# TIDA-01576_ADS8686S_AFE_Pg4-5V-15V_Split.net
KiCad netlist of a schematic drawn in Altium Designer
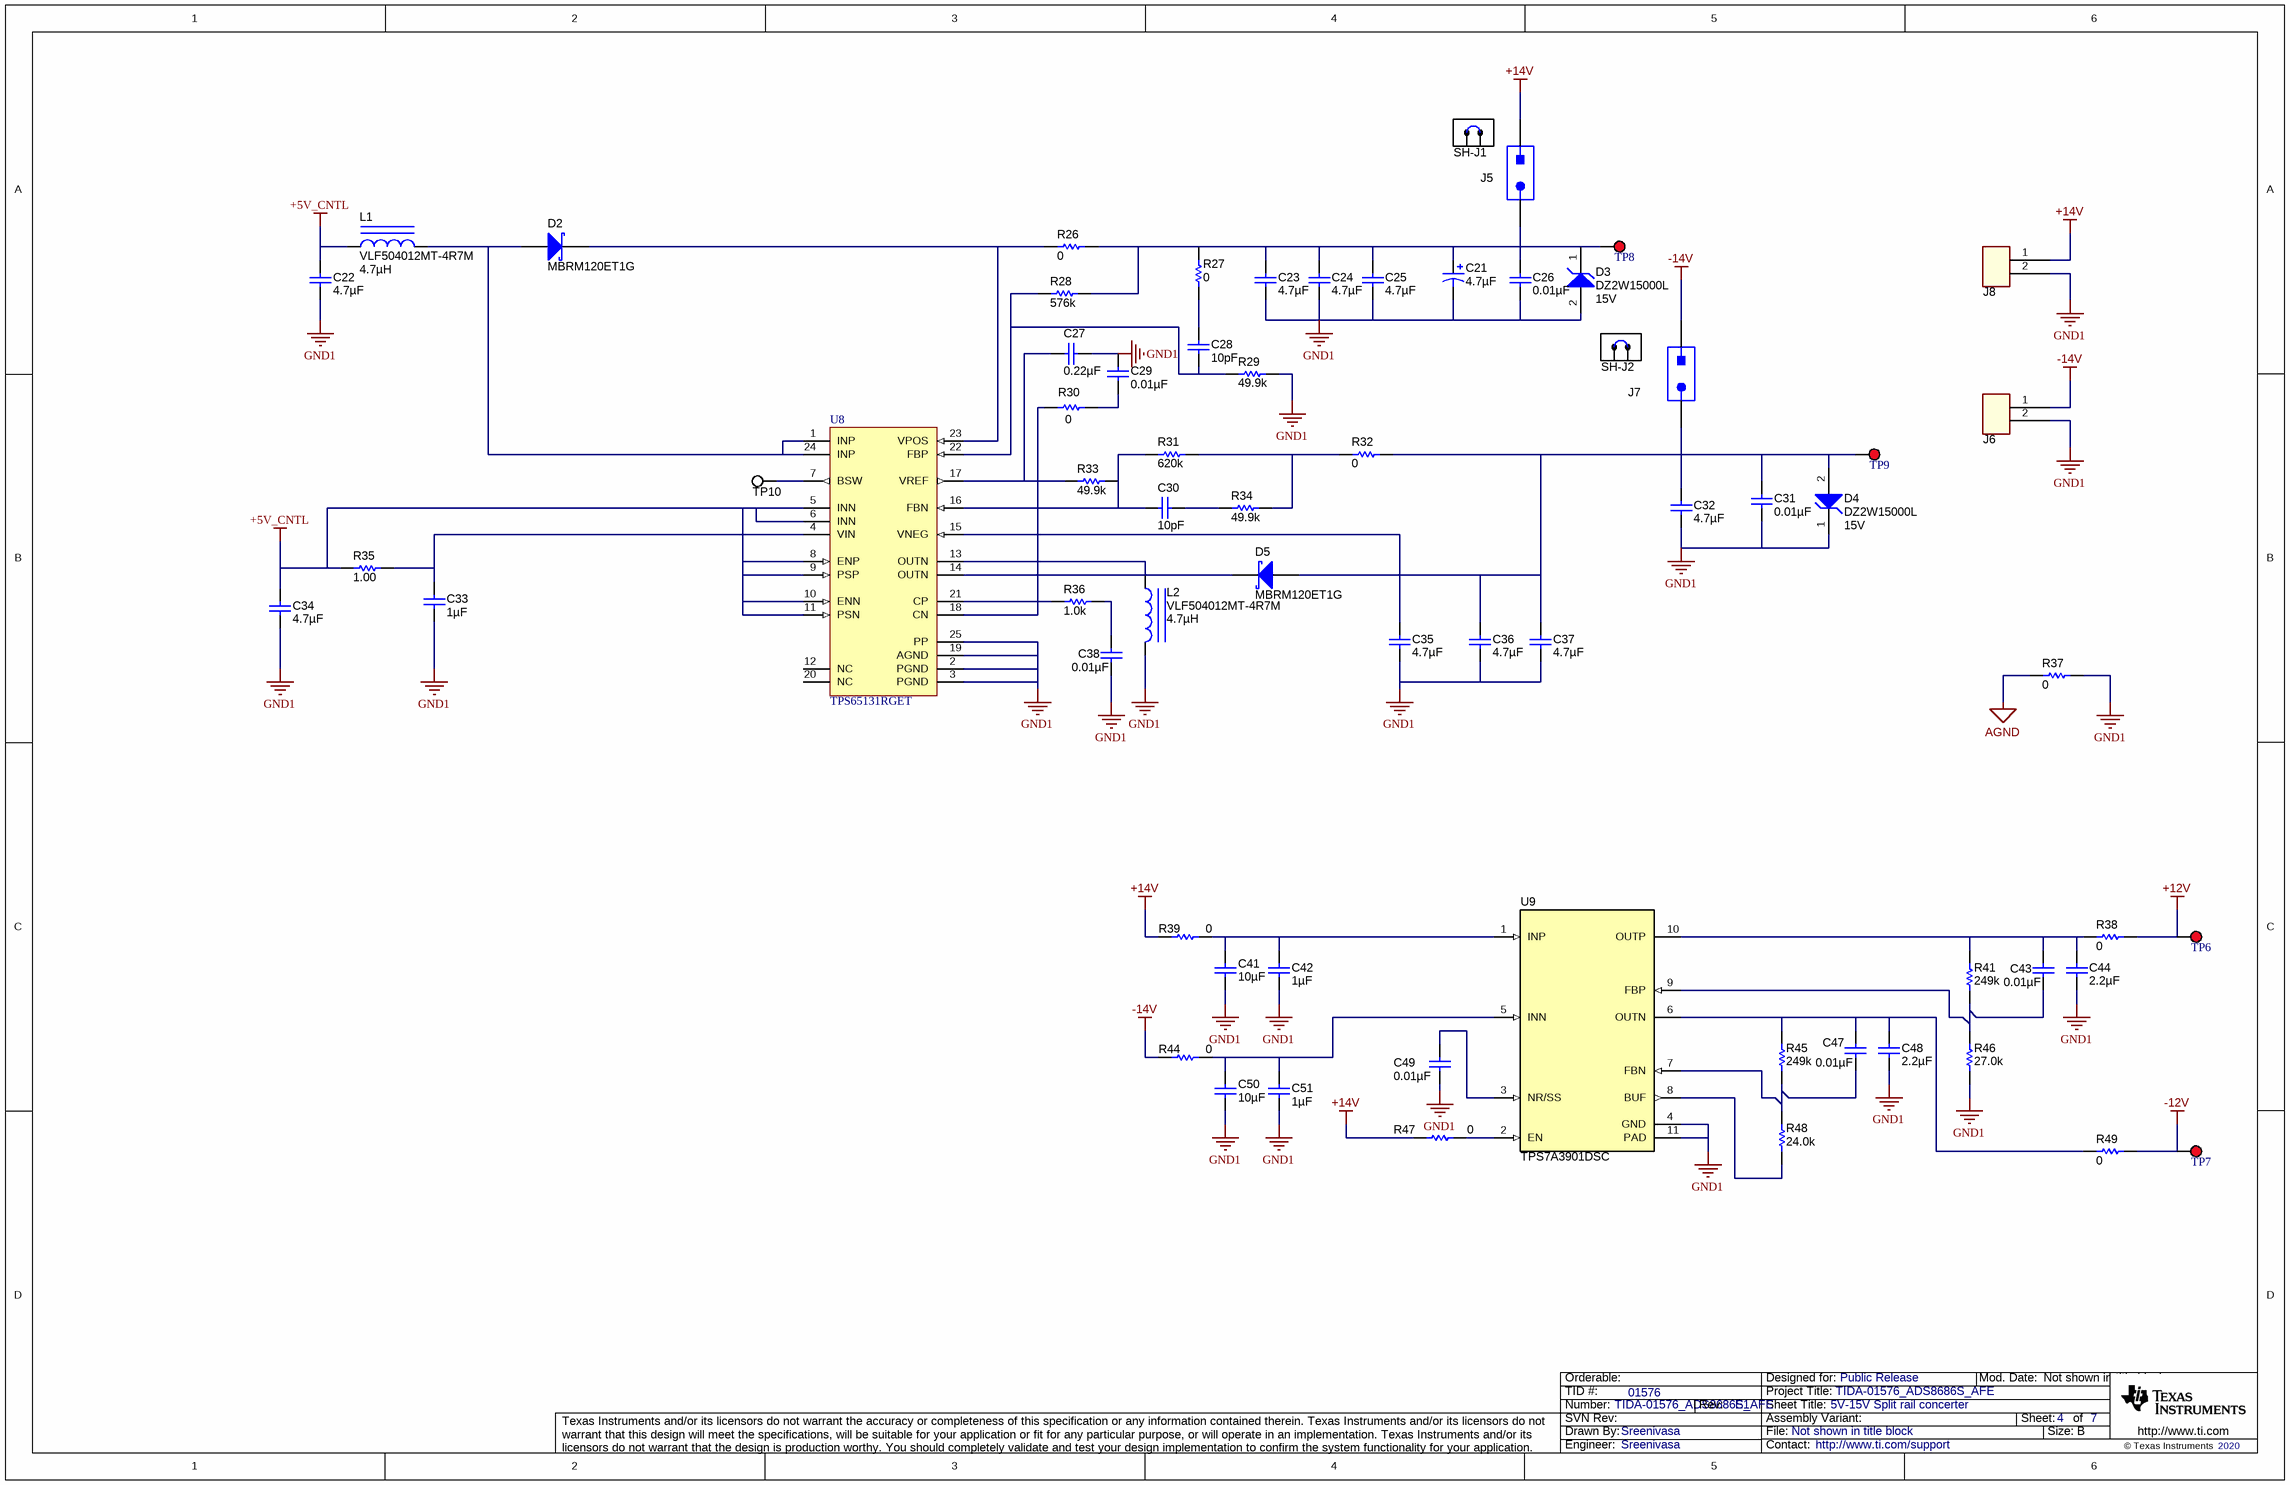
[diagram p0: TIDA-01576_ADS8686S_AFE_Pg4-5V-15V Split rail converter.SchDoc]

(export (version "E")
  (design (tool "Eeschema 10.0.6"))
  (components
    (comp (ref "C21")
      (value "293D475X9025C2TE3")
      (footprint "6032-28")
      (description "CAP, TA, 4.7 µF, 25 V, +/- 10%, 2 ohm, SMD")
      (fields
        (field (name "VALUEDISPLAYED") "4.7µF")
        (field (name "MANUFACTURER") "Vishay-Sprague")
        (field (name "PUBLISHER") "Texas Instruments")
      )
      (libsource (lib "Capacitor_Tantalum") (part "293D475X9025C2TE3"))
    )
    (comp (ref "C22")
      (value "C3216X7R1E475M160AC")
      (footprint "1206")
      (description "CAP, CERM, 4.7 µF, 25 V, +/- 20%, X7R, 1206")
      (fields
        (field (name "VALUEDISPLAYED") "4.7µF")
        (field (name "MANUFACTURER") "TDK")
        (field (name "PUBLISHER") "Texas Instruments")
      )
      (libsource (lib "Capacitor_Ceramic") (part "C3216X7R1E475M"))
    )
    (comp (ref "C23")
      (value "C3216X7R1E475M160AC")
      (footprint "1206")
      (description "CAP, CERM, 4.7 µF, 25 V, +/- 20%, X7R, 1206")
      (fields
        (field (name "VALUEDISPLAYED") "4.7µF")
        (field (name "MANUFACTURER") "TDK")
        (field (name "PUBLISHER") "Texas Instruments")
      )
      (libsource (lib "Capacitor_Ceramic") (part "C3216X7R1E475M"))
    )
    (comp (ref "C24")
      (value "C3216X7R1E475M160AC")
      (footprint "1206")
      (description "CAP, CERM, 4.7 µF, 25 V, +/- 20%, X7R, 1206")
      (fields
        (field (name "VALUEDISPLAYED") "4.7µF")
        (field (name "MANUFACTURER") "TDK")
        (field (name "PUBLISHER") "Texas Instruments")
      )
      (libsource (lib "Capacitor_Ceramic") (part "C3216X7R1E475M"))
    )
    (comp (ref "C25")
      (value "C3216X7R1E475M160AC")
      (footprint "1206")
      (description "CAP, CERM, 4.7 µF, 25 V, +/- 20%, X7R, 1206")
      (fields
        (field (name "VALUEDISPLAYED") "4.7µF")
        (field (name "MANUFACTURER") "TDK")
        (field (name "PUBLISHER") "Texas Instruments")
      )
      (libsource (lib "Capacitor_Ceramic") (part "C3216X7R1E475M"))
    )
    (comp (ref "C26")
      (value "GRM188R70J103KA01D")
      (footprint "0603")
      (description "CAP, CERM, 0.01 µF, 6.3 V, +/- 10%, X7R, 0603")
      (fields
        (field (name "VALUEDISPLAYED") "0.01µF")
        (field (name "MANUFACTURER") "MuRata")
        (field (name "PUBLISHER") "Texas Instruments")
      )
      (libsource (lib "Capacitor_Ceramic") (part "GRM188R70J103KA01D"))
    )
    (comp (ref "C27")
      (value "C0603C224K9RACTU")
      (footprint "0603")
      (description "CAP, CERM, 0.22 µF, 6.3 V, +/- 10%, X7R, 0603")
      (fields
        (field (name "VALUEDISPLAYED") "0.22µF")
        (field (name "MANUFACTURER") "Kemet")
        (field (name "PUBLISHER") "Texas Instruments")
      )
      (libsource (lib "Capacitor_Ceramic") (part "C0603C224K4RACTU"))
    )
    (comp (ref "C28")
      (value "C0603C100J5GACTU")
      (footprint "0603")
      (description "CAP, CERM, 10 pF, 50 V, +/- 5%, C0G/NP0, 0603")
      (fields
        (field (name "VALUEDISPLAYED") "10pF")
        (field (name "MANUFACTURER") "Kemet")
        (field (name "PUBLISHER") "Texas Instruments")
      )
      (libsource (lib "Capacitor_Ceramic") (part "C0603C100J5GACTU"))
    )
    (comp (ref "C29")
      (value "GRM188R70J103KA01D")
      (footprint "0603")
      (description "CAP, CERM, 0.01 µF, 6.3 V, +/- 10%, X7R, 0603")
      (fields
        (field (name "VALUEDISPLAYED") "0.01µF")
        (field (name "MANUFACTURER") "MuRata")
        (field (name "PUBLISHER") "Texas Instruments")
      )
      (libsource (lib "Capacitor_Ceramic") (part "GRM188R70J103KA01D"))
    )
    (comp (ref "C30")
      (value "C0603C100J5GACTU")
      (footprint "0603")
      (description "CAP, CERM, 10 pF, 50 V, +/- 5%, C0G/NP0, 0603")
      (fields
        (field (name "VALUEDISPLAYED") "10pF")
        (field (name "MANUFACTURER") "Kemet")
        (field (name "PUBLISHER") "Texas Instruments")
      )
      (libsource (lib "Capacitor_Ceramic") (part "C0603C100J5GACTU"))
    )
    (comp (ref "C31")
      (value "GRM188R70J103KA01D")
      (footprint "0603")
      (description "CAP, CERM, 0.01 µF, 6.3 V, +/- 10%, X7R, 0603")
      (fields
        (field (name "VALUEDISPLAYED") "0.01µF")
        (field (name "MANUFACTURER") "MuRata")
        (field (name "PUBLISHER") "Texas Instruments")
      )
      (libsource (lib "Capacitor_Ceramic") (part "GRM188R70J103KA01D"))
    )
    (comp (ref "C32")
      (value "C3216X7R1E475M160AC")
      (footprint "1206")
      (description "CAP, CERM, 4.7 µF, 25 V, +/- 20%, X7R, 1206")
      (fields
        (field (name "VALUEDISPLAYED") "4.7µF")
        (field (name "MANUFACTURER") "TDK")
        (field (name "PUBLISHER") "Texas Instruments")
      )
      (libsource (lib "Capacitor_Ceramic") (part "C3216X7R1E475M"))
    )
    (comp (ref "C33")
      (value "GRM188R61E105KA12D")
      (footprint "0603")
      (description "CAP, CERM, 1 µF, 25 V, +/- 10%, X5R, 0603")
      (fields
        (field (name "VALUEDISPLAYED") "1µF")
        (field (name "MANUFACTURER") "MuRata")
        (field (name "PUBLISHER") "Texas Instruments")
      )
      (libsource (lib "Capacitor_Ceramic") (part "GRM188R61E105KA12D"))
    )
    (comp (ref "C34")
      (value "C3216X7R1E475M160AC")
      (footprint "1206")
      (description "CAP, CERM, 4.7 µF, 25 V, +/- 20%, X7R, 1206")
      (fields
        (field (name "VALUEDISPLAYED") "4.7µF")
        (field (name "MANUFACTURER") "TDK")
        (field (name "PUBLISHER") "Texas Instruments")
      )
      (libsource (lib "Capacitor_Ceramic") (part "C3216X7R1E475M"))
    )
    (comp (ref "C35")
      (value "C3216X7R1E475M160AC")
      (footprint "1206")
      (description "CAP, CERM, 4.7 µF, 25 V, +/- 20%, X7R, 1206")
      (fields
        (field (name "VALUEDISPLAYED") "4.7µF")
        (field (name "MANUFACTURER") "TDK")
        (field (name "PUBLISHER") "Texas Instruments")
      )
      (libsource (lib "Capacitor_Ceramic") (part "C3216X7R1E475M"))
    )
    (comp (ref "C36")
      (value "C3216X7R1E475M160AC")
      (footprint "1206")
      (description "CAP, CERM, 4.7 µF, 25 V, +/- 20%, X7R, 1206")
      (fields
        (field (name "VALUEDISPLAYED") "4.7µF")
        (field (name "MANUFACTURER") "TDK")
        (field (name "PUBLISHER") "Texas Instruments")
      )
      (libsource (lib "Capacitor_Ceramic") (part "C3216X7R1E475M"))
    )
    (comp (ref "C37")
      (value "C3216X7R1E475M160AC")
      (footprint "1206")
      (description "CAP, CERM, 4.7 µF, 25 V, +/- 20%, X7R, 1206")
      (fields
        (field (name "VALUEDISPLAYED") "4.7µF")
        (field (name "MANUFACTURER") "TDK")
        (field (name "PUBLISHER") "Texas Instruments")
      )
      (libsource (lib "Capacitor_Ceramic") (part "C3216X7R1E475M"))
    )
    (comp (ref "C38")
      (value "GRM188R70J103KA01D")
      (footprint "0603")
      (description "CAP, CERM, 0.01 µF, 6.3 V, +/- 10%, X7R, 0603")
      (fields
        (field (name "VALUEDISPLAYED") "0.01µF")
        (field (name "MANUFACTURER") "MuRata")
        (field (name "PUBLISHER") "Texas Instruments")
      )
      (libsource (lib "Capacitor_Ceramic") (part "GRM188R70J103KA01D"))
    )
    (comp (ref "C41")
      (value "~")
      (footprint "1210")
      (description "CAP, CERM, 10uF, 35V, +/-20%, X7R, 1210")
      (fields
        (field (name "PARTNUMBER") "GMK325AB7106MM-T")
        (field (name "VALUEDISPLAYED") "10µF")
        (field (name "MANUFACTURER") "Taiyo Yuden")
        (field (name "PUBLISHER") "Texas Instruments")
      )
      (libsource (lib "Capacitor_Ceramic") (part "GMK325AB7106MM-T"))
    )
    (comp (ref "C42")
      (value "GRM188R61E105KA12D")
      (footprint "0603")
      (description "CAP, CERM, 1 µF, 25 V, +/- 10%, X5R, 0603")
      (fields
        (field (name "VALUEDISPLAYED") "1µF")
        (field (name "MANUFACTURER") "MuRata")
        (field (name "PUBLISHER") "Texas Instruments")
      )
      (libsource (lib "Capacitor_Ceramic") (part "GRM188R61E105KA12D"))
    )
    (comp (ref "C43")
      (value "GRM188R70J103KA01D")
      (footprint "0603")
      (description "CAP, CERM, 0.01 µF, 6.3 V, +/- 10%, X7R, 0603")
      (fields
        (field (name "VALUEDISPLAYED") "0.01µF")
        (field (name "MANUFACTURER") "MuRata")
        (field (name "PUBLISHER") "Texas Instruments")
      )
      (libsource (lib "Capacitor_Ceramic") (part "GRM188R70J103KA01D"))
    )
    (comp (ref "C44")
      (value "C0805C225K8RACTU")
      (footprint "0805_HV")
      (description "CAP, CERM, 2.2uF, 10V, +/-10%, X7R, 0805")
      (fields
        (field (name "VALUEDISPLAYED") "2.2µF")
        (field (name "MANUFACTURER") "Kemet")
        (field (name "PUBLISHER") "Texas Instruments")
      )
      (libsource (lib "Capacitor_Ceramic") (part "C0805C225K8RACTU"))
    )
    (comp (ref "C47")
      (value "GRM188R70J103KA01D")
      (footprint "0603")
      (description "CAP, CERM, 0.01 µF, 6.3 V, +/- 10%, X7R, 0603")
      (fields
        (field (name "VALUEDISPLAYED") "0.01µF")
        (field (name "MANUFACTURER") "MuRata")
        (field (name "PUBLISHER") "Texas Instruments")
      )
      (libsource (lib "Capacitor_Ceramic") (part "GRM188R70J103KA01D"))
    )
    (comp (ref "C48")
      (value "C0805C225K8RACTU")
      (footprint "0805_HV")
      (description "CAP, CERM, 2.2uF, 10V, +/-10%, X7R, 0805")
      (fields
        (field (name "VALUEDISPLAYED") "2.2µF")
        (field (name "MANUFACTURER") "Kemet")
        (field (name "PUBLISHER") "Texas Instruments")
      )
      (libsource (lib "Capacitor_Ceramic") (part "C0805C225K8RACTU"))
    )
    (comp (ref "C49")
      (value "GRM188R70J103KA01D")
      (footprint "0603")
      (description "CAP, CERM, 0.01 µF, 6.3 V, +/- 10%, X7R, 0603")
      (fields
        (field (name "VALUEDISPLAYED") "0.01µF")
        (field (name "MANUFACTURER") "MuRata")
        (field (name "PUBLISHER") "Texas Instruments")
      )
      (libsource (lib "Capacitor_Ceramic") (part "GRM188R70J103KA01D"))
    )
    (comp (ref "C50")
      (value "~")
      (footprint "1210")
      (description "CAP, CERM, 10uF, 35V, +/-20%, X7R, 1210")
      (fields
        (field (name "PARTNUMBER") "GMK325AB7106MM-T")
        (field (name "VALUEDISPLAYED") "10µF")
        (field (name "MANUFACTURER") "Taiyo Yuden")
        (field (name "PUBLISHER") "Texas Instruments")
      )
      (libsource (lib "Capacitor_Ceramic") (part "GMK325AB7106MM-T"))
    )
    (comp (ref "C51")
      (value "GRM188R61E105KA12D")
      (footprint "0603")
      (description "CAP, CERM, 1 µF, 25 V, +/- 10%, X5R, 0603")
      (fields
        (field (name "VALUEDISPLAYED") "1µF")
        (field (name "MANUFACTURER") "MuRata")
        (field (name "PUBLISHER") "Texas Instruments")
      )
      (libsource (lib "Capacitor_Ceramic") (part "GRM188R61E105KA12D"))
    )
    (comp (ref "D2")
      (value "MBRM120ET1G")
      (footprint "POWERMITE")
      (description "Diode, Schottky, 20 V, 1 A, POWERMITE")
      (fields (field (name "MANUFACTURER") "ON Semiconductor") (field (name "PUBLISHER") "Texas Instruments"))
      (libsource (lib "Diode") (part "MBRM120ET1G"))
    )
    (comp (ref "D3")
      (value "DZ2W15000L")
      (footprint "SOD-123")
      (description "Diode, Zener, 15V, 1W, SOD-123")
      (fields
        (field (name "MANUFACTURER") "Panasonic")
        (field (name "ALTIUM_VALUE") "15V")
        (field (name "PUBLISHER") "Texas Instruments")
      )
      (libsource (lib "TI-INDIA-ALTIUM") (part "DZ2W15000L"))
    )
    (comp (ref "D4")
      (value "DZ2W15000L")
      (footprint "SOD-123")
      (description "Diode, Zener, 15V, 1W, SOD-123")
      (fields
        (field (name "MANUFACTURER") "Panasonic")
        (field (name "ALTIUM_VALUE") "15V")
        (field (name "PUBLISHER") "Texas Instruments")
      )
      (libsource (lib "TI-INDIA-ALTIUM") (part "DZ2W15000L"))
    )
    (comp (ref "D5")
      (value "MBRM120ET1G")
      (footprint "POWERMITE")
      (description "Diode, Schottky, 20 V, 1 A, POWERMITE")
      (fields (field (name "MANUFACTURER") "ON Semiconductor") (field (name "PUBLISHER") "Texas Instruments"))
      (libsource (lib "Diode") (part "MBRM120ET1G"))
    )
    (comp (ref "J5")
      (value "5-146280-2")
      (footprint "TSW-102-07-G-S")
      (description "Header, 100mil, 2x1, Gold, TH")
      (fields
        (field (name "MANUFACTURER") "TE Connectivity")
        (field (name "SYMBOLCREATOR") "a0412235")
        (field (name "PUBLISHER") "Texas Instruments")
      )
      (libsource (lib "Connectors_Samtec") (part "TSW-102-07-G-S"))
    )
    (comp (ref "J6")
      (value "CON-OSTVN02A150")
      (footprint "CN2_MTB_P100_PD80_D1.1_S5.54X6.5_STACK")
      (description "Terminal Block, 4x1, 2.54mm, TH")
      (fields
        (field (name "PARTNUMBER") "OSTVN02A150")
        (field (name "MANUFACTURER") "On Shore Technology Inc")
        (field (name "SYMBOLCREATOR") "x0120606")
        (field (name "PUBLISHER") "TI")
      )
      (libsource (lib "TI-INDIA-ALTIUM") (part "CON-OSTVN02A150"))
    )
    (comp (ref "J7")
      (value "5-146280-2")
      (footprint "TSW-102-07-G-S")
      (description "Header, 100mil, 2x1, Gold, TH")
      (fields
        (field (name "MANUFACTURER") "TE Connectivity")
        (field (name "SYMBOLCREATOR") "a0412235")
        (field (name "PUBLISHER") "Texas Instruments")
      )
      (libsource (lib "Connectors_Samtec") (part "TSW-102-07-G-S"))
    )
    (comp (ref "J8")
      (value "CON-OSTVN02A150")
      (footprint "CN2_MTB_P100_PD80_D1.1_S5.54X6.5_STACK")
      (description "Terminal Block, 4x1, 2.54mm, TH")
      (fields
        (field (name "PARTNUMBER") "OSTVN02A150")
        (field (name "MANUFACTURER") "On Shore Technology Inc")
        (field (name "SYMBOLCREATOR") "x0120606")
        (field (name "PUBLISHER") "TI")
      )
      (libsource (lib "TI-INDIA-ALTIUM") (part "CON-OSTVN02A150"))
    )
    (comp (ref "L1")
      (value "VLF504012MT-4R7M")
      (footprint "IND_VLF504012")
      (description "Inductor, Shielded, Ferrite, 4.7uH, 1.83A, 0.1 ohm, SMD")
      (fields
        (field (name "VALUEDISPLAYED") "4.7µH")
        (field (name "MANUFACTURER") "TDK")
        (field (name "PUBLISHER") "Texas Instruments")
      )
      (libsource (lib "Inductor") (part "VLF504012MT-4R7M"))
    )
    (comp (ref "L2")
      (value "VLF504012MT-4R7M")
      (footprint "IND_VLF504012")
      (description "Inductor, Shielded, Ferrite, 4.7uH, 1.83A, 0.1 ohm, SMD")
      (fields
        (field (name "VALUEDISPLAYED") "4.7µH")
        (field (name "MANUFACTURER") "TDK")
        (field (name "PUBLISHER") "Texas Instruments")
      )
      (libsource (lib "Inductor") (part "VLF504012MT-4R7M"))
    )
    (comp (ref "R26")
      (value "0")
      (footprint "1206")
      (description "RES, 0 ohm, 5%, 0.25W, 1206")
      (fields
        (field (name "PARTNUMBER") "CRCW12060000Z0EA")
        (field (name "MANUFACTURER") "Vishay-Dale")
        (field (name "PUBLISHER") "Texas Instruments")
      )
      (libsource (lib "Resistor_1206") (part "CRCW12060000Z0EA"))
    )
    (comp (ref "R27")
      (value "CRCW06030000Z0EA")
      (footprint "0603")
      (description "RES, 0, 5%, 0.1 W, 0603")
      (fields
        (field (name "VALUEDISPLAYED") "0")
        (field (name "MANUFACTURER") "Vishay-Dale")
        (field (name "PUBLISHER") "Texas Instruments")
      )
      (libsource (lib "Resistor_0603") (part "CRCW06030000Z0EA"))
    )
    (comp (ref "R28")
      (value "CRCW0603576KFKEA")
      (footprint "0603")
      (description "RES, 576 k, 1%, 0.1 W, 0603")
      (fields
        (field (name "VALUEDISPLAYED") "576k")
        (field (name "MANUFACTURER") "Vishay-Dale")
        (field (name "PUBLISHER") "Texas Instruments")
      )
      (libsource (lib "Resistor_0603") (part "CRCW0603576KFKEA"))
    )
    (comp (ref "R29")
      (value "RG1608P-4992-B-T5")
      (footprint "0603")
      (description "RES, 49.9 k, 0.1%, 0.1 W, 0603")
      (fields
        (field (name "VALUEDISPLAYED") "49.9k")
        (field (name "MANUFACTURER") "Susumu Co Ltd")
        (field (name "PUBLISHER") "Texas Instruments")
      )
      (libsource (lib "Resistor_0603") (part "RG1608P-4992-B-T5"))
    )
    (comp (ref "R30")
      (value "CRCW06030000Z0EA")
      (footprint "0603")
      (description "RES, 0, 5%, 0.1 W, 0603")
      (fields
        (field (name "VALUEDISPLAYED") "0")
        (field (name "MANUFACTURER") "Vishay-Dale")
        (field (name "PUBLISHER") "Texas Instruments")
      )
      (libsource (lib "Resistor_0603") (part "CRCW06030000Z0EA"))
    )
    (comp (ref "R31")
      (value "CRCW0603620KFKEA")
      (footprint "0603")
      (description "RES SMD 620K OHM 1% 1/10W 0603")
      (fields
        (field (name "VALUEDISPLAYED") "620k")
        (field (name "MANUFACTURER") "Vishay-Dale")
        (field (name "PUBLISHER") "Texas Instruments")
      )
      (libsource (lib "Resistor_0603") (part "RC0603FR-07620KL"))
    )
    (comp (ref "R32")
      (value "CRCW06030000Z0EA")
      (footprint "0603")
      (description "RES, 0, 5%, 0.1 W, 0603")
      (fields
        (field (name "VALUEDISPLAYED") "0")
        (field (name "MANUFACTURER") "Vishay-Dale")
        (field (name "PUBLISHER") "Texas Instruments")
      )
      (libsource (lib "Resistor_0603") (part "CRCW06030000Z0EA"))
    )
    (comp (ref "R33")
      (value "RG1608P-4992-B-T5")
      (footprint "0603")
      (description "RES, 49.9 k, 0.1%, 0.1 W, 0603")
      (fields
        (field (name "VALUEDISPLAYED") "49.9k")
        (field (name "MANUFACTURER") "Susumu Co Ltd")
        (field (name "PUBLISHER") "Texas Instruments")
      )
      (libsource (lib "Resistor_0603") (part "RG1608P-4992-B-T5"))
    )
    (comp (ref "R34")
      (value "RG1608P-4992-B-T5")
      (footprint "0603")
      (description "RES, 49.9 k, 0.1%, 0.1 W, 0603")
      (fields
        (field (name "VALUEDISPLAYED") "49.9k")
        (field (name "MANUFACTURER") "Susumu Co Ltd")
        (field (name "PUBLISHER") "Texas Instruments")
      )
      (libsource (lib "Resistor_0603") (part "RG1608P-4992-B-T5"))
    )
    (comp (ref "R35")
      (value "CR0603-J/-1R0ELF")
      (footprint "0603")
      (description "RES SMD 1 OHM 5% 1/10W 0603")
      (fields
        (field (name "VALUEDISPLAYED") "1.00")
        (field (name "MANUFACTURER") "Bourns inc")
        (field (name "PUBLISHER") "Texas Instruments")
      )
      (libsource (lib "Resistor_0603") (part "RT0603DRE071RL"))
    )
    (comp (ref "R36")
      (value "CRCW06031K00JNEA")
      (footprint "0603")
      (description "RES, 1.0 k, 5%, 0.1 W, 0603")
      (fields
        (field (name "VALUEDISPLAYED") "1.0k")
        (field (name "MANUFACTURER") "Vishay-Dale")
        (field (name "PUBLISHER") "Texas Instruments")
      )
      (libsource (lib "Resistor_0603") (part "CRCW06031K00JNEA"))
    )
    (comp (ref "R37")
      (value "0")
      (footprint "0805_HV")
      (description "RES, 0 ohm, 5%, 0.125W, 0805")
      (fields
        (field (name "PARTNUMBER") "CRCW08050000Z0EA")
        (field (name "MANUFACTURER") "Vishay-Dale")
        (field (name "PUBLISHER") "Texas Instruments")
      )
      (libsource (lib "Resistor_0805") (part "CRCW0805330KJNEA"))
    )
    (comp (ref "R38")
      (value "CRCW06030000Z0EA")
      (footprint "0603")
      (description "RES, 0, 5%, 0.1 W, 0603")
      (fields
        (field (name "VALUEDISPLAYED") "0")
        (field (name "MANUFACTURER") "Vishay-Dale")
        (field (name "PUBLISHER") "Texas Instruments")
      )
      (libsource (lib "Resistor_0603") (part "CRCW06030000Z0EA"))
    )
    (comp (ref "R39")
      (value "CRCW06030000Z0EA")
      (footprint "0603")
      (description "RES, 0, 5%, 0.1 W, 0603")
      (fields
        (field (name "VALUEDISPLAYED") "0")
        (field (name "MANUFACTURER") "Vishay-Dale")
        (field (name "PUBLISHER") "Texas Instruments")
      )
      (libsource (lib "Resistor_0603") (part "CRCW06030000Z0EA"))
    )
    (comp (ref "R41")
      (value "CRCW0603249KFKEA")
      (footprint "0603")
      (description "RES, 249 k, 1%, 0.1 W, 0603")
      (fields
        (field (name "VALUEDISPLAYED") "249k")
        (field (name "MANUFACTURER") "Vishay-Dale")
        (field (name "PUBLISHER") "Texas Instruments")
      )
      (libsource (lib "Resistor_0603") (part "CRCW0603249KFKEA"))
    )
    (comp (ref "R44")
      (value "CRCW06030000Z0EA")
      (footprint "0603")
      (description "RES, 0, 5%, 0.1 W, 0603")
      (fields
        (field (name "VALUEDISPLAYED") "0")
        (field (name "MANUFACTURER") "Vishay-Dale")
        (field (name "PUBLISHER") "Texas Instruments")
      )
      (libsource (lib "Resistor_0603") (part "CRCW06030000Z0EA"))
    )
    (comp (ref "R45")
      (value "CRCW0603249KFKEA")
      (footprint "0603")
      (description "RES, 249 k, 1%, 0.1 W, 0603")
      (fields
        (field (name "VALUEDISPLAYED") "249k")
        (field (name "MANUFACTURER") "Vishay-Dale")
        (field (name "PUBLISHER") "Texas Instruments")
      )
      (libsource (lib "Resistor_0603") (part "CRCW0603249KFKEA"))
    )
    (comp (ref "R46")
      (value "RC0603FR-0727KL")
      (footprint "0603")
      (description "RES, 27.0 k, 1%, 0.1 W, 0603")
      (fields
        (field (name "VALUEDISPLAYED") "27.0k")
        (field (name "MANUFACTURER") "Yageo America")
        (field (name "PUBLISHER") "Texas Instruments")
      )
      (libsource (lib "Resistor_0603") (part "RC0603FR-0727KL"))
    )
    (comp (ref "R47")
      (value "CRCW06030000Z0EA")
      (footprint "0603")
      (description "RES, 0, 5%, 0.1 W, 0603")
      (fields
        (field (name "VALUEDISPLAYED") "0")
        (field (name "MANUFACTURER") "Vishay-Dale")
        (field (name "PUBLISHER") "Texas Instruments")
      )
      (libsource (lib "Resistor_0603") (part "CRCW06030000Z0EA"))
    )
    (comp (ref "R48")
      (value "RC0603FR-0724KL")
      (footprint "0603")
      (description "RES, 24.0 k, 1%, 0.1 W, 0603")
      (fields
        (field (name "VALUEDISPLAYED") "24.0k")
        (field (name "MANUFACTURER") "Yageo America")
        (field (name "PUBLISHER") "Texas Instruments")
      )
      (libsource (lib "Resistor_0603") (part "RC0603FR-0724KL"))
    )
    (comp (ref "R49")
      (value "CRCW06030000Z0EA")
      (footprint "0603")
      (description "RES, 0, 5%, 0.1 W, 0603")
      (fields
        (field (name "VALUEDISPLAYED") "0")
        (field (name "MANUFACTURER") "Vishay-Dale")
        (field (name "PUBLISHER") "Texas Instruments")
      )
      (libsource (lib "Resistor_0603") (part "CRCW06030000Z0EA"))
    )
    (comp (ref "SH-J1")
      (value "881545-2")
      (footprint "TE_881545-2")
      (description "Shunt, 100mil, Gold plated, Black")
      (fields (field (name "MANUFACTURER") "TE Connectivity") (field (name "PUBLISHER") "Texas Instruments"))
      (libsource (lib "Hardware") (part "881545-2"))
    )
    (comp (ref "SH-J2")
      (value "881545-2")
      (footprint "TE_881545-2")
      (description "Shunt, 100mil, Gold plated, Black")
      (fields (field (name "MANUFACTURER") "TE Connectivity") (field (name "PUBLISHER") "Texas Instruments"))
      (libsource (lib "Hardware") (part "881545-2"))
    )
    (comp (ref "TP6")
      (value "5000")
      (footprint "Keystone5000")
      (description "Test Point, Miniature, Red, TH")
      (fields (field (name "MANUFACTURER") "Keystone") (field (name "PUBLISHER") "Texas Instruments"))
      (libsource (lib "Connectors_Keystone") (part "5000"))
    )
    (comp (ref "TP7")
      (value "5000")
      (footprint "Keystone5000")
      (description "Test Point, Miniature, Red, TH")
      (fields (field (name "MANUFACTURER") "Keystone") (field (name "PUBLISHER") "Texas Instruments"))
      (libsource (lib "Connectors_Keystone") (part "5000"))
    )
    (comp (ref "TP8")
      (value "5000")
      (footprint "Keystone5000")
      (description "Test Point, Miniature, Red, TH")
      (fields (field (name "MANUFACTURER") "Keystone") (field (name "PUBLISHER") "Texas Instruments"))
      (libsource (lib "Connectors_Keystone") (part "5000"))
    )
    (comp (ref "TP9")
      (value "5000")
      (footprint "Keystone5000")
      (description "Test Point, Miniature, Red, TH")
      (fields (field (name "MANUFACTURER") "Keystone") (field (name "PUBLISHER") "Texas Instruments"))
      (libsource (lib "Connectors_Keystone") (part "5000"))
    )
    (comp (ref "TP10")
      (value "5002")
      (footprint "Keystone5002")
      (description "Test Point, Miniature, White, TH")
      (fields (field (name "MANUFACTURER") "Keystone") (field (name "PUBLISHER") "Texas Instruments"))
      (libsource (lib "Connectors_Keystone") (part "5002"))
    )
    (comp (ref "U8")
      (value "TPS65131RGET")
      (footprint "RGE0024B")
      (fields
        (field (name "MANUFACTURER") "Texas Instruments")
        (field (name "ALTERNATE PARTNUMBER") "Equivalent")
      )
      (libsource (lib "TI Power Management Lighting and Display") (part "TPS65131RGET"))
    )
    (comp (ref "U9")
      (value "TPS7A3901DSC")
      (footprint "DSC0010J")
      (fields
        (field (name "MANUFACTURER") "Texas Instruments")
        (field (name "SYMBOLCREATOR") "Altium")
        (field (name "PUBLISHER") "Texas Instruments")
      )
      (libsource (lib "TI_Pre_RTM") (part "TPS7A3901DSC"))
    )
  )
  (nets
    (net (code "1") (name "+5V_CNTL") (class "Default")
      (node (ref "C22") (pin "1") (pinfunction "1_1") (pintype "passive"))
      (node (ref "C34") (pin "1") (pinfunction "1_1") (pintype "passive"))
      (node (ref "L1") (pin "1") (pinfunction "1_1") (pintype "passive"))
      (node (ref "R35") (pin "1") (pinfunction "1_1") (pintype "passive"))
      (node (ref "U8") (pin "10") (pinfunction "ENN_10") (pintype "input"))
      (node (ref "U8") (pin "11") (pinfunction "PSN_11") (pintype "input"))
      (node (ref "U8") (pin "5") (pinfunction "INN_5") (pintype "power_in"))
      (node (ref "U8") (pin "6") (pinfunction "INN_6") (pintype "power_in"))
      (node (ref "U8") (pin "8") (pinfunction "ENP_8") (pintype "input"))
      (node (ref "U8") (pin "9") (pinfunction "PSP_9") (pintype "input"))
    )
    (net (code "2") (name "+12V") (class "Default")
      (node (ref "R38") (pin "2") (pinfunction "2_2") (pintype "passive"))
      (node (ref "TP6") (pin "1") (pintype "passive"))
    )
    (net (code "3") (name "+14V") (class "Default")
      (node (ref "J5") (pin "1") (pinfunction "1_1") (pintype "passive"))
      (node (ref "J8") (pin "1") (pinfunction "1_1") (pintype "passive"))
      (node (ref "R39") (pin "1") (pinfunction "1_1") (pintype "passive"))
      (node (ref "R47") (pin "1") (pinfunction "1_1") (pintype "passive"))
    )
    (net (code "4") (name "-12V") (class "Default")
      (node (ref "R49") (pin "2") (pinfunction "2_2") (pintype "passive"))
      (node (ref "TP7") (pin "1") (pintype "passive"))
    )
    (net (code "5") (name "-14V") (class "Default")
      (node (ref "J6") (pin "1") (pinfunction "1_1") (pintype "passive"))
      (node (ref "J7") (pin "1") (pinfunction "1_1") (pintype "passive"))
      (node (ref "R44") (pin "1") (pinfunction "1_1") (pintype "passive"))
    )
    (net (code "6") (name "AGND") (class "Default")
      (node (ref "R37") (pin "1") (pinfunction "1_1") (pintype "passive"))
    )
    (net (code "7") (name "GND1") (class "Default")
      (node (ref "C21") (pin "2") (pinfunction "-_2") (pintype "passive"))
      (node (ref "C22") (pin "2") (pinfunction "2_2") (pintype "passive"))
      (node (ref "C23") (pin "2") (pinfunction "2_2") (pintype "passive"))
      (node (ref "C24") (pin "2") (pinfunction "2_2") (pintype "passive"))
      (node (ref "C25") (pin "2") (pinfunction "2_2") (pintype "passive"))
      (node (ref "C26") (pin "2") (pinfunction "2_2") (pintype "passive"))
      (node (ref "C27") (pin "1") (pinfunction "1_1") (pintype "passive"))
      (node (ref "C29") (pin "1") (pinfunction "1_1") (pintype "passive"))
      (node (ref "C31") (pin "2") (pinfunction "2_2") (pintype "passive"))
      (node (ref "C32") (pin "2") (pinfunction "2_2") (pintype "passive"))
      (node (ref "C33") (pin "2") (pinfunction "2_2") (pintype "passive"))
      (node (ref "C34") (pin "2") (pinfunction "2_2") (pintype "passive"))
      (node (ref "C35") (pin "2") (pinfunction "2_2") (pintype "passive"))
      (node (ref "C36") (pin "2") (pinfunction "2_2") (pintype "passive"))
      (node (ref "C37") (pin "2") (pinfunction "2_2") (pintype "passive"))
      (node (ref "C38") (pin "2") (pinfunction "2_2") (pintype "passive"))
      (node (ref "C41") (pin "1") (pinfunction "1_1") (pintype "passive"))
      (node (ref "C42") (pin "2") (pinfunction "2_2") (pintype "passive"))
      (node (ref "C44") (pin "2") (pinfunction "2_2") (pintype "passive"))
      (node (ref "C48") (pin "2") (pinfunction "2_2") (pintype "passive"))
      (node (ref "C49") (pin "2") (pinfunction "2_2") (pintype "passive"))
      (node (ref "C50") (pin "1") (pinfunction "1_1") (pintype "passive"))
      (node (ref "C51") (pin "2") (pinfunction "2_2") (pintype "passive"))
      (node (ref "D3") (pin "2") (pinfunction "A_2") (pintype "passive"))
      (node (ref "D4") (pin "1") (pinfunction "K_1") (pintype "passive"))
      (node (ref "J6") (pin "2") (pinfunction "2_2") (pintype "passive"))
      (node (ref "J8") (pin "2") (pinfunction "2_2") (pintype "passive"))
      (node (ref "L2") (pin "2") (pinfunction "2_2") (pintype "passive"))
      (node (ref "R29") (pin "2") (pinfunction "2_2") (pintype "passive"))
      (node (ref "R37") (pin "2") (pinfunction "2_2") (pintype "passive"))
      (node (ref "R46") (pin "1") (pinfunction "1_1") (pintype "passive"))
      (node (ref "U8") (pin "19") (pinfunction "AGND_19") (pintype "power_in"))
      (node (ref "U8") (pin "2") (pinfunction "PGND_2") (pintype "power_in"))
      (node (ref "U8") (pin "25") (pinfunction "PP_25") (pintype "power_in"))
      (node (ref "U8") (pin "3") (pinfunction "PGND_3") (pintype "power_in"))
      (node (ref "U9") (pin "11") (pinfunction "PAD_11") (pintype "power_in"))
      (node (ref "U9") (pin "4") (pinfunction "GND_4") (pintype "power_in"))
    )
    (net (code "8") (name "Net-(C21-+)") (class "Default")
      (node (ref "C21") (pin "1") (pinfunction "+_1") (pintype "passive"))
      (node (ref "C23") (pin "1") (pinfunction "1_1") (pintype "passive"))
      (node (ref "C24") (pin "1") (pinfunction "1_1") (pintype "passive"))
      (node (ref "C25") (pin "1") (pinfunction "1_1") (pintype "passive"))
      (node (ref "C26") (pin "1") (pinfunction "1_1") (pintype "passive"))
      (node (ref "D3") (pin "1") (pinfunction "K_1") (pintype "passive"))
      (node (ref "J5") (pin "2") (pinfunction "2_2") (pintype "passive"))
      (node (ref "R26") (pin "2") (pinfunction "2_2") (pintype "passive"))
      (node (ref "R27") (pin "2") (pinfunction "2_2") (pintype "passive"))
      (node (ref "R28") (pin "2") (pinfunction "2_2") (pintype "passive"))
      (node (ref "TP8") (pin "1") (pintype "passive"))
    )
    (net (code "9") (name "Net-(C28-Pad1)") (class "Default")
      (node (ref "C28") (pin "1") (pinfunction "1_1") (pintype "passive"))
      (node (ref "R27") (pin "1") (pinfunction "1_1") (pintype "passive"))
    )
    (net (code "10") (name "Net-(C29-Pad2)") (class "Default")
      (node (ref "C29") (pin "2") (pinfunction "2_2") (pintype "passive"))
      (node (ref "R30") (pin "2") (pinfunction "2_2") (pintype "passive"))
    )
    (net (code "11") (name "Net-(C30-Pad1)") (class "Default")
      (node (ref "C30") (pin "1") (pinfunction "1_1") (pintype "passive"))
      (node (ref "R34") (pin "1") (pinfunction "1_1") (pintype "passive"))
    )
    (net (code "12") (name "Net-(C38-Pad1)") (class "Default")
      (node (ref "C38") (pin "1") (pinfunction "1_1") (pintype "passive"))
      (node (ref "R36") (pin "2") (pinfunction "2_2") (pintype "passive"))
    )
    (net (code "13") (name "Net-(D2-A)") (class "Default")
      (node (ref "D2") (pin "2") (pinfunction "A_2") (pintype "passive"))
      (node (ref "L1") (pin "2") (pinfunction "2_2") (pintype "passive"))
      (node (ref "U8") (pin "1") (pinfunction "INP_1") (pintype "power_in"))
      (node (ref "U8") (pin "24") (pinfunction "INP_24") (pintype "power_in"))
    )
    (net (code "14") (name "Net-(D2-K)") (class "Default")
      (node (ref "D2") (pin "1") (pinfunction "K_1") (pintype "passive"))
      (node (ref "R26") (pin "1") (pinfunction "1_1") (pintype "passive"))
      (node (ref "U8") (pin "23") (pinfunction "VPOS_23") (pintype "input"))
    )
    (net (code "15") (name "Net-(D4-A)") (class "Default")
      (node (ref "C31") (pin "1") (pinfunction "1_1") (pintype "passive"))
      (node (ref "C32") (pin "1") (pinfunction "1_1") (pintype "passive"))
      (node (ref "C35") (pin "1") (pinfunction "1_1") (pintype "passive"))
      (node (ref "C36") (pin "1") (pinfunction "1_1") (pintype "passive"))
      (node (ref "C37") (pin "1") (pinfunction "1_1") (pintype "passive"))
      (node (ref "D4") (pin "2") (pinfunction "A_2") (pintype "passive"))
      (node (ref "D5") (pin "2") (pinfunction "A_2") (pintype "passive"))
      (node (ref "J7") (pin "2") (pinfunction "2_2") (pintype "passive"))
      (node (ref "R32") (pin "2") (pinfunction "2_2") (pintype "passive"))
      (node (ref "TP9") (pin "1") (pintype "passive"))
      (node (ref "U8") (pin "15") (pinfunction "VNEG_15") (pintype "input"))
    )
    (net (code "16") (name "Net-(D5-K)") (class "Default")
      (node (ref "D5") (pin "1") (pinfunction "K_1") (pintype "passive"))
      (node (ref "L2") (pin "1") (pinfunction "1_1") (pintype "passive"))
      (node (ref "U8") (pin "13") (pinfunction "OUTN_13") (pintype "power_in"))
      (node (ref "U8") (pin "14") (pinfunction "OUTN_14") (pintype "power_in"))
    )
    (net (code "17") (name "Net-(R31-Pad2)") (class "Default")
      (node (ref "R31") (pin "2") (pinfunction "2_2") (pintype "passive"))
      (node (ref "R32") (pin "1") (pinfunction "1_1") (pintype "passive"))
      (node (ref "R34") (pin "2") (pinfunction "2_2") (pintype "passive"))
    )
    (net (code "18") (name "Net-(U8-BSW)") (class "Default")
      (node (ref "TP10") (pin "1") (pintype "passive"))
      (node (ref "U8") (pin "7") (pinfunction "BSW_7") (pintype "output"))
    )
    (net (code "19") (name "Net-(U8-CN)") (class "Default")
      (node (ref "R30") (pin "1") (pinfunction "1_1") (pintype "passive"))
      (node (ref "U8") (pin "18") (pinfunction "CN_18") (pintype "passive"))
    )
    (net (code "20") (name "Net-(U8-CP)") (class "Default")
      (node (ref "R36") (pin "1") (pinfunction "1_1") (pintype "passive"))
      (node (ref "U8") (pin "21") (pinfunction "CP_21") (pintype "passive"))
    )
    (net (code "21") (name "Net-(U8-FBN)") (class "Default")
      (node (ref "C30") (pin "2") (pinfunction "2_2") (pintype "passive"))
      (node (ref "R31") (pin "1") (pinfunction "1_1") (pintype "passive"))
      (node (ref "R33") (pin "2") (pinfunction "2_2") (pintype "passive"))
      (node (ref "U8") (pin "16") (pinfunction "FBN_16") (pintype "input"))
    )
    (net (code "22") (name "Net-(U8-FBP)") (class "Default")
      (node (ref "C28") (pin "2") (pinfunction "2_2") (pintype "passive"))
      (node (ref "R28") (pin "1") (pinfunction "1_1") (pintype "passive"))
      (node (ref "R29") (pin "1") (pinfunction "1_1") (pintype "passive"))
      (node (ref "U8") (pin "22") (pinfunction "FBP_22") (pintype "input"))
    )
    (net (code "23") (name "Net-(U8-VIN)") (class "Default")
      (node (ref "C33") (pin "1") (pinfunction "1_1") (pintype "passive"))
      (node (ref "R35") (pin "2") (pinfunction "2_2") (pintype "passive"))
      (node (ref "U8") (pin "4") (pinfunction "VIN_4") (pintype "power_in"))
    )
    (net (code "24") (name "Net-(U8-VREF)") (class "Default")
      (node (ref "C27") (pin "2") (pinfunction "2_2") (pintype "passive"))
      (node (ref "R33") (pin "1") (pinfunction "1_1") (pintype "passive"))
      (node (ref "U8") (pin "17") (pinfunction "VREF_17") (pintype "output"))
    )
    (net (code "25") (name "Net-(U9-BUF)") (class "Default")
      (node (ref "R48") (pin "1") (pinfunction "1_1") (pintype "passive"))
      (node (ref "U9") (pin "8") (pinfunction "BUF_8") (pintype "output"))
    )
    (net (code "26") (name "Net-(U9-EN)") (class "Default")
      (node (ref "R47") (pin "2") (pinfunction "2_2") (pintype "passive"))
      (node (ref "U9") (pin "2") (pinfunction "EN_2") (pintype "input"))
    )
    (net (code "27") (name "Net-(U9-FBN)") (class "Default")
      (node (ref "C47") (pin "2") (pinfunction "2_2") (pintype "passive"))
      (node (ref "R45") (pin "1") (pinfunction "1_1") (pintype "passive"))
      (node (ref "R48") (pin "2") (pinfunction "2_2") (pintype "passive"))
      (node (ref "U9") (pin "7") (pinfunction "FBN_7") (pintype "input"))
    )
    (net (code "28") (name "Net-(U9-FBP)") (class "Default")
      (node (ref "C43") (pin "2") (pinfunction "2_2") (pintype "passive"))
      (node (ref "R41") (pin "1") (pinfunction "1_1") (pintype "passive"))
      (node (ref "R46") (pin "2") (pinfunction "2_2") (pintype "passive"))
      (node (ref "U9") (pin "9") (pinfunction "FBP_9") (pintype "input"))
    )
    (net (code "29") (name "Net-(U9-INN)") (class "Default")
      (node (ref "C50") (pin "2") (pinfunction "2_2") (pintype "passive"))
      (node (ref "C51") (pin "1") (pinfunction "1_1") (pintype "passive"))
      (node (ref "R44") (pin "2") (pinfunction "2_2") (pintype "passive"))
      (node (ref "U9") (pin "5") (pinfunction "INN_5") (pintype "input"))
    )
    (net (code "30") (name "Net-(U9-INP)") (class "Default")
      (node (ref "C41") (pin "2") (pinfunction "2_2") (pintype "passive"))
      (node (ref "C42") (pin "1") (pinfunction "1_1") (pintype "passive"))
      (node (ref "R39") (pin "2") (pinfunction "2_2") (pintype "passive"))
      (node (ref "U9") (pin "1") (pinfunction "INP_1") (pintype "input"))
    )
    (net (code "31") (name "Net-(U9-NR{slash}SS)") (class "Default")
      (node (ref "C49") (pin "1") (pinfunction "1_1") (pintype "passive"))
      (node (ref "U9") (pin "3") (pinfunction "NR/SS_3") (pintype "input"))
    )
    (net (code "32") (name "Net-(U9-OUTN)") (class "Default")
      (node (ref "C47") (pin "1") (pinfunction "1_1") (pintype "passive"))
      (node (ref "C48") (pin "1") (pinfunction "1_1") (pintype "passive"))
      (node (ref "R45") (pin "2") (pinfunction "2_2") (pintype "passive"))
      (node (ref "R49") (pin "1") (pinfunction "1_1") (pintype "passive"))
      (node (ref "U9") (pin "6") (pinfunction "OUTN_6") (pintype "power_in"))
    )
    (net (code "33") (name "Net-(U9-OUTP)") (class "Default")
      (node (ref "C43") (pin "1") (pinfunction "1_1") (pintype "passive"))
      (node (ref "C44") (pin "1") (pinfunction "1_1") (pintype "passive"))
      (node (ref "R38") (pin "1") (pinfunction "1_1") (pintype "passive"))
      (node (ref "R41") (pin "2") (pinfunction "2_2") (pintype "passive"))
      (node (ref "U9") (pin "10") (pinfunction "OUTP_10") (pintype "power_in"))
    )
    (net (code "34") (name "unconnected-(U8-NC-Pad12)") (class "Default")
      (node (ref "U8") (pin "12") (pinfunction "NC_12") (pintype "passive"))
    )
    (net (code "35") (name "unconnected-(U8-NC-Pad20)") (class "Default")
      (node (ref "U8") (pin "20") (pinfunction "NC_20") (pintype "passive"))
    )
  )
)
